# USB.net
KiCad netlist of a schematic drawn in Altium Designer
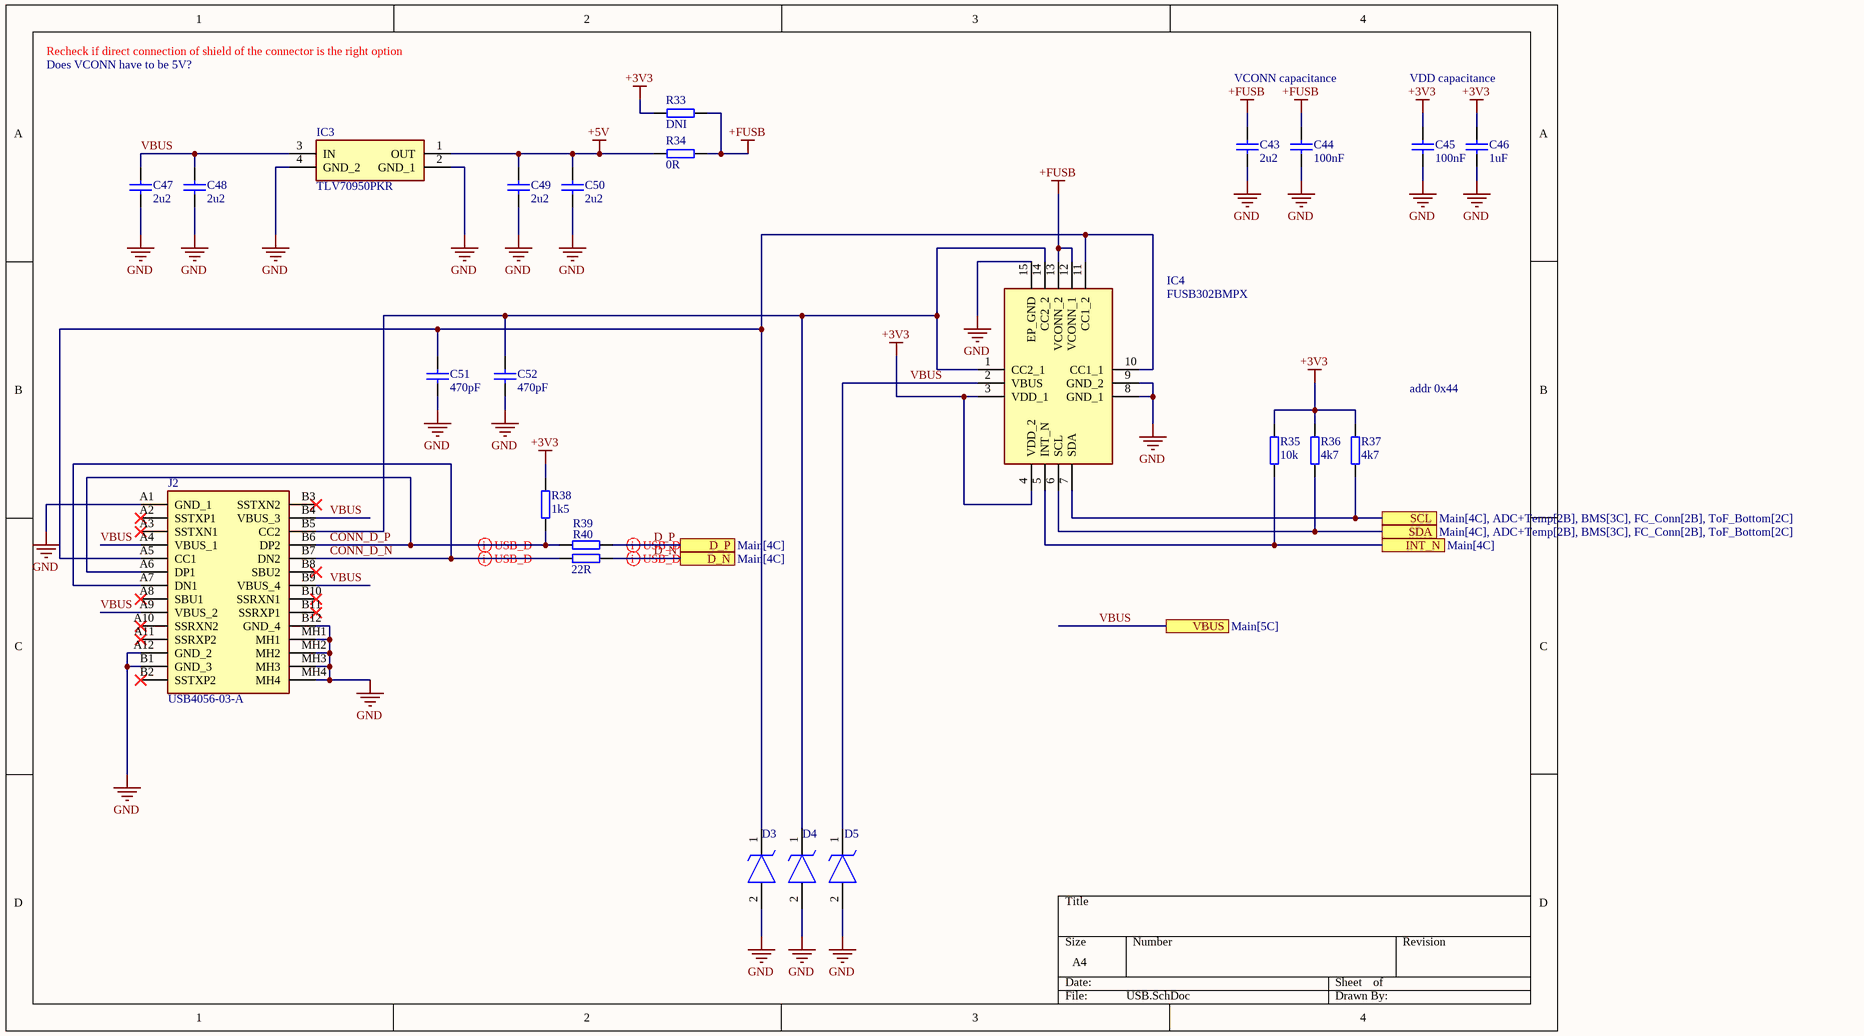
[diagram p0: USB.SchDoc]

(export (version "E")
  (design (tool "Eeschema 10.0.6"))
  (components
    (comp (ref "C43")
      (value "2u2")
      (footprint "CAP0603")
      (fields (field (name "VOLTAGE") "50V") (field (name "Comment") "Cap0603"))
      (libsource (lib "capacitorsSMD") (part "Cap0603"))
    )
    (comp (ref "C44")
      (value "100nF")
      (footprint "CAP0402")
      (fields (field (name "VOLTAGE") "6V3") (field (name "Comment") "Cap0402"))
      (libsource (lib "capacitorsSMD") (part "Cap0402"))
    )
    (comp (ref "C45")
      (value "100nF")
      (footprint "CAP0402")
      (fields (field (name "VOLTAGE") "6V3") (field (name "Comment") "Cap0402"))
      (libsource (lib "capacitorsSMD") (part "Cap0402"))
    )
    (comp (ref "C46")
      (value "1uF")
      (footprint "CAP0402")
      (fields (field (name "VOLTAGE") "6V3") (field (name "Comment") "Cap0402"))
      (libsource (lib "capacitorsSMD") (part "Cap0402"))
    )
    (comp (ref "C47")
      (value "2u2")
      (footprint "CAP0603")
      (fields (field (name "VOLTAGE") "50V") (field (name "Comment") "Cap0603"))
      (libsource (lib "capacitorsSMD") (part "Cap0603"))
    )
    (comp (ref "C48")
      (value "2u2")
      (footprint "CAP0603")
      (fields (field (name "VOLTAGE") "50V") (field (name "Comment") "Cap0603"))
      (libsource (lib "capacitorsSMD") (part "Cap0603"))
    )
    (comp (ref "C49")
      (value "2u2")
      (footprint "CAP0603")
      (fields (field (name "VOLTAGE") "50V") (field (name "Comment") "Cap0603"))
      (libsource (lib "capacitorsSMD") (part "Cap0603"))
    )
    (comp (ref "C50")
      (value "2u2")
      (footprint "CAP0603")
      (fields (field (name "VOLTAGE") "50V") (field (name "Comment") "Cap0603"))
      (libsource (lib "capacitorsSMD") (part "Cap0603"))
    )
    (comp (ref "C51")
      (value "470pF")
      (footprint "CAP0402")
      (fields (field (name "VOLTAGE") "val") (field (name "Comment") "Cap0402"))
      (libsource (lib "capacitorsSMD") (part "Cap0402"))
    )
    (comp (ref "C52")
      (value "470pF")
      (footprint "CAP0402")
      (fields (field (name "VOLTAGE") "val") (field (name "Comment") "Cap0402"))
      (libsource (lib "capacitorsSMD") (part "Cap0402"))
    )
    (comp (ref "D3")
      (value "D1213A-01LP4-7B")
      (footprint "SamacSys:D1213A01LP47B")
      (description "TVS Diode (Uni-directional)")
      (fields (field (name "MOUSER PART NUMBER") "621-D1213A-01LP4-7B"))
      (libsource (lib "*") (part "D1213A-01LP4-7B"))
    )
    (comp (ref "D4")
      (value "D1213A-01LP4-7B")
      (footprint "SamacSys:D1213A01LP47B")
      (description "TVS Diode (Uni-directional)")
      (fields (field (name "MOUSER PART NUMBER") "621-D1213A-01LP4-7B"))
      (libsource (lib "*") (part "D1213A-01LP4-7B"))
    )
    (comp (ref "D5")
      (value "DF2S24FS,L3M")
      (footprint "SamacSys:SODFL1006X45N")
      (description "TVS Diode (Uni-directional)")
      (fields (field (name "MOUSER PART NUMBER") "757-DF2S24FSL3M"))
      (libsource (lib "*") (part "DF2S24FS,L3M"))
    )
    (comp (ref "IC3")
      (value "TLV70950PKR")
      (footprint "SamacSys:TL431AQPKG3")
      (description "Integrated Circuit")
      (fields (field (name "MOUSER PART NUMBER") "595-TLV70950PKR"))
      (libsource (lib "*") (part "TLV70950PKR"))
    )
    (comp (ref "IC4")
      (value "FUSB302BMPX")
      (footprint "SamacSys:QFN50P250X250X80-15N")
      (description "Integrated Circuit")
      (fields (field (name "MOUSER PART NUMBER") "512-FUSB302BMPX"))
      (libsource (lib "*") (part "FUSB302BMPX"))
    )
    (comp (ref "J2")
      (value "USB4056-03-A")
      (footprint "SamacSys:USB405603A")
      (description "Connector")
      (fields (field (name "MOUSER PART NUMBER") "640-USB4056-03-A"))
      (libsource (lib "*") (part "USB4056-03-A"))
    )
    (comp (ref "R33")
      (value "DNI")
      (footprint "RES0402")
      (fields (field (name "Comment") "Res0402"))
      (libsource (lib "resistorSMD") (part "Res0402"))
    )
    (comp (ref "R34")
      (value "0R")
      (footprint "RES0402")
      (fields (field (name "Comment") "Res0402"))
      (libsource (lib "resistorSMD") (part "Res0402"))
    )
    (comp (ref "R35")
      (value "10k")
      (footprint "RES0402")
      (fields (field (name "Comment") "Res0402"))
      (libsource (lib "resistorSMD") (part "Res0402"))
    )
    (comp (ref "R36")
      (value "4k7")
      (footprint "RES0402")
      (fields (field (name "Comment") "Res0402"))
      (libsource (lib "resistorSMD") (part "Res0402"))
    )
    (comp (ref "R37")
      (value "4k7")
      (footprint "RES0402")
      (fields (field (name "Comment") "Res0402"))
      (libsource (lib "resistorSMD") (part "Res0402"))
    )
    (comp (ref "R38")
      (value "1k5")
      (footprint "RES0402")
      (fields (field (name "Comment") "Res0402"))
      (libsource (lib "resistorSMD") (part "Res0402"))
    )
    (comp (ref "R39")
      (value "Res0402")
      (footprint "RES0402")
      (libsource (lib "resistorSMD") (part "Res0402"))
    )
    (comp (ref "R40")
      (value "22R")
      (footprint "RES0402")
      (fields (field (name "Comment") "Res0402"))
      (libsource (lib "resistorSMD") (part "Res0402"))
    )
  )
  (nets
    (net (code "1") (name "+3V3") (class "Default")
      (node (ref "C45") (pin "2") (pinfunction "2_2") (pintype "passive"))
      (node (ref "C46") (pin "2") (pinfunction "2_2") (pintype "passive"))
      (node (ref "IC4") (pin "3") (pinfunction "VDD_1_3") (pintype "passive"))
      (node (ref "IC4") (pin "4") (pinfunction "VDD_2_4") (pintype "passive"))
      (node (ref "R33") (pin "2") (pinfunction "2_2") (pintype "passive"))
      (node (ref "R35") (pin "2") (pinfunction "2_2") (pintype "passive"))
      (node (ref "R36") (pin "2") (pinfunction "2_2") (pintype "passive"))
      (node (ref "R37") (pin "2") (pinfunction "2_2") (pintype "passive"))
      (node (ref "R38") (pin "2") (pinfunction "2_2") (pintype "passive"))
    )
    (net (code "2") (name "+5V") (class "Default")
      (node (ref "C49") (pin "2") (pinfunction "2_2") (pintype "passive"))
      (node (ref "C50") (pin "2") (pinfunction "2_2") (pintype "passive"))
      (node (ref "IC3") (pin "1") (pinfunction "OUT_1") (pintype "passive"))
      (node (ref "R34") (pin "2") (pinfunction "2_2") (pintype "passive"))
    )
    (net (code "3") (name "+FUSB") (class "Default")
      (node (ref "C43") (pin "2") (pinfunction "2_2") (pintype "passive"))
      (node (ref "C44") (pin "2") (pinfunction "2_2") (pintype "passive"))
      (node (ref "IC4") (pin "12") (pinfunction "VCONN_1_12") (pintype "passive"))
      (node (ref "IC4") (pin "13") (pinfunction "VCONN_2_13") (pintype "passive"))
      (node (ref "R33") (pin "1") (pinfunction "1_1") (pintype "passive"))
      (node (ref "R34") (pin "1") (pinfunction "1_1") (pintype "passive"))
    )
    (net (code "4") (name "/CONN_D_N") (class "Default")
      (node (ref "J2") (pin "A7") (pinfunction "DN1_A7") (pintype "passive"))
      (node (ref "J2") (pin "B7") (pinfunction "DN2_B7") (pintype "passive"))
      (node (ref "R40") (pin "1") (pinfunction "1_1") (pintype "passive"))
    )
    (net (code "5") (name "/CONN_D_P") (class "Default")
      (node (ref "J2") (pin "A6") (pinfunction "DP1_A6") (pintype "passive"))
      (node (ref "J2") (pin "B6") (pinfunction "DP2_B6") (pintype "passive"))
      (node (ref "R38") (pin "1") (pinfunction "1_1") (pintype "passive"))
      (node (ref "R39") (pin "1") (pinfunction "1_1") (pintype "passive"))
    )
    (net (code "6") (name "/D_N") (class "Default")
      (node (ref "R40") (pin "2") (pinfunction "2_2") (pintype "passive"))
    )
    (net (code "7") (name "/D_P") (class "Default")
      (node (ref "R39") (pin "2") (pinfunction "2_2") (pintype "passive"))
    )
    (net (code "8") (name "/INT_N") (class "Default")
      (node (ref "IC4") (pin "5") (pinfunction "INT_N_5") (pintype "passive"))
      (node (ref "R35") (pin "1") (pinfunction "1_1") (pintype "passive"))
    )
    (net (code "9") (name "/SCL") (class "Default")
      (node (ref "IC4") (pin "7") (pinfunction "SDA_7") (pintype "passive"))
      (node (ref "R37") (pin "1") (pinfunction "1_1") (pintype "passive"))
    )
    (net (code "10") (name "/SDA") (class "Default")
      (node (ref "IC4") (pin "6") (pinfunction "SCL_6") (pintype "passive"))
      (node (ref "R36") (pin "1") (pinfunction "1_1") (pintype "passive"))
    )
    (net (code "11") (name "/VBUS") (class "Default")
      (node (ref "C47") (pin "2") (pinfunction "2_2") (pintype "passive"))
      (node (ref "C48") (pin "2") (pinfunction "2_2") (pintype "passive"))
      (node (ref "D5") (pin "1") (pinfunction "K_1") (pintype "passive"))
      (node (ref "IC3") (pin "3") (pinfunction "IN_3") (pintype "passive"))
      (node (ref "IC4") (pin "2") (pinfunction "VBUS_2") (pintype "passive"))
      (node (ref "J2") (pin "A4") (pinfunction "VBUS_1_A4") (pintype "passive"))
      (node (ref "J2") (pin "A9") (pinfunction "VBUS_2_A9") (pintype "passive"))
      (node (ref "J2") (pin "B4") (pinfunction "VBUS_3_B4") (pintype "passive"))
      (node (ref "J2") (pin "B9") (pinfunction "VBUS_4_B9") (pintype "passive"))
    )
    (net (code "12") (name "GND") (class "Default")
      (node (ref "C43") (pin "1") (pinfunction "1_1") (pintype "passive"))
      (node (ref "C44") (pin "1") (pinfunction "1_1") (pintype "passive"))
      (node (ref "C45") (pin "1") (pinfunction "1_1") (pintype "passive"))
      (node (ref "C46") (pin "1") (pinfunction "1_1") (pintype "passive"))
      (node (ref "C47") (pin "1") (pinfunction "1_1") (pintype "passive"))
      (node (ref "C48") (pin "1") (pinfunction "1_1") (pintype "passive"))
      (node (ref "C49") (pin "1") (pinfunction "1_1") (pintype "passive"))
      (node (ref "C50") (pin "1") (pinfunction "1_1") (pintype "passive"))
      (node (ref "C51") (pin "1") (pinfunction "1_1") (pintype "passive"))
      (node (ref "C52") (pin "1") (pinfunction "1_1") (pintype "passive"))
      (node (ref "D3") (pin "2") (pinfunction "A_2") (pintype "passive"))
      (node (ref "D4") (pin "2") (pinfunction "A_2") (pintype "passive"))
      (node (ref "D5") (pin "2") (pinfunction "A_2") (pintype "passive"))
      (node (ref "IC3") (pin "2") (pinfunction "GND_1_2") (pintype "passive"))
      (node (ref "IC3") (pin "4") (pinfunction "GND_2_4") (pintype "passive"))
      (node (ref "IC4") (pin "15") (pinfunction "EP_GND_15") (pintype "passive"))
      (node (ref "IC4") (pin "8") (pinfunction "GND_1_8") (pintype "passive"))
      (node (ref "IC4") (pin "9") (pinfunction "GND_2_9") (pintype "passive"))
      (node (ref "J2") (pin "A1") (pinfunction "GND_1_A1") (pintype "passive"))
      (node (ref "J2") (pin "A12") (pinfunction "GND_2_A12") (pintype "passive"))
      (node (ref "J2") (pin "B1") (pinfunction "GND_3_B1") (pintype "passive"))
      (node (ref "J2") (pin "B12") (pinfunction "GND_4_B12") (pintype "passive"))
      (node (ref "J2") (pin "MH1") (pinfunction "MH1_MH1") (pintype "passive"))
      (node (ref "J2") (pin "MH2") (pinfunction "MH2_MH2") (pintype "passive"))
      (node (ref "J2") (pin "MH3") (pinfunction "MH3_MH3") (pintype "passive"))
      (node (ref "J2") (pin "MH4") (pinfunction "MH4_MH4") (pintype "passive"))
    )
    (net (code "13") (name "Net-(D3-K)") (class "Default")
      (node (ref "C51") (pin "2") (pinfunction "2_2") (pintype "passive"))
      (node (ref "D3") (pin "1") (pinfunction "K_1") (pintype "passive"))
      (node (ref "IC4") (pin "10") (pinfunction "CC1_1_10") (pintype "passive"))
      (node (ref "IC4") (pin "11") (pinfunction "CC1_2_11") (pintype "passive"))
      (node (ref "J2") (pin "A5") (pinfunction "CC1_A5") (pintype "passive"))
    )
    (net (code "14") (name "Net-(D4-K)") (class "Default")
      (node (ref "C52") (pin "2") (pinfunction "2_2") (pintype "passive"))
      (node (ref "D4") (pin "1") (pinfunction "K_1") (pintype "passive"))
      (node (ref "IC4") (pin "1") (pinfunction "CC2_1_1") (pintype "passive"))
      (node (ref "IC4") (pin "14") (pinfunction "CC2_2_14") (pintype "passive"))
      (node (ref "J2") (pin "B5") (pinfunction "CC2_B5") (pintype "passive"))
    )
    (net (code "15") (name "unconnected-(J2-SBU1-PadA8)") (class "Default")
      (node (ref "J2") (pin "A8") (pinfunction "SBU1_A8") (pintype "passive+no_connect"))
    )
    (net (code "16") (name "unconnected-(J2-SBU2-PadB8)") (class "Default")
      (node (ref "J2") (pin "B8") (pinfunction "SBU2_B8") (pintype "passive+no_connect"))
    )
    (net (code "17") (name "unconnected-(J2-SSRXN1-PadB10)") (class "Default")
      (node (ref "J2") (pin "B10") (pinfunction "SSRXN1_B10") (pintype "passive+no_connect"))
    )
    (net (code "18") (name "unconnected-(J2-SSRXN2-PadA10)") (class "Default")
      (node (ref "J2") (pin "A10") (pinfunction "SSRXN2_A10") (pintype "passive+no_connect"))
    )
    (net (code "19") (name "unconnected-(J2-SSRXP1-PadB11)") (class "Default")
      (node (ref "J2") (pin "B11") (pinfunction "SSRXP1_B11") (pintype "passive+no_connect"))
    )
    (net (code "20") (name "unconnected-(J2-SSRXP2-PadA11)") (class "Default")
      (node (ref "J2") (pin "A11") (pinfunction "SSRXP2_A11") (pintype "passive+no_connect"))
    )
    (net (code "21") (name "unconnected-(J2-SSTXN1-PadA3)") (class "Default")
      (node (ref "J2") (pin "A3") (pinfunction "SSTXN1_A3") (pintype "passive+no_connect"))
    )
    (net (code "22") (name "unconnected-(J2-SSTXN2-PadB3)") (class "Default")
      (node (ref "J2") (pin "B3") (pinfunction "SSTXN2_B3") (pintype "passive+no_connect"))
    )
    (net (code "23") (name "unconnected-(J2-SSTXP1-PadA2)") (class "Default")
      (node (ref "J2") (pin "A2") (pinfunction "SSTXP1_A2") (pintype "passive+no_connect"))
    )
    (net (code "24") (name "unconnected-(J2-SSTXP2-PadB2)") (class "Default")
      (node (ref "J2") (pin "B2") (pinfunction "SSTXP2_B2") (pintype "passive+no_connect"))
    )
  )
)
